# EARS.net
KiCad netlist of a schematic drawn in EAGLE
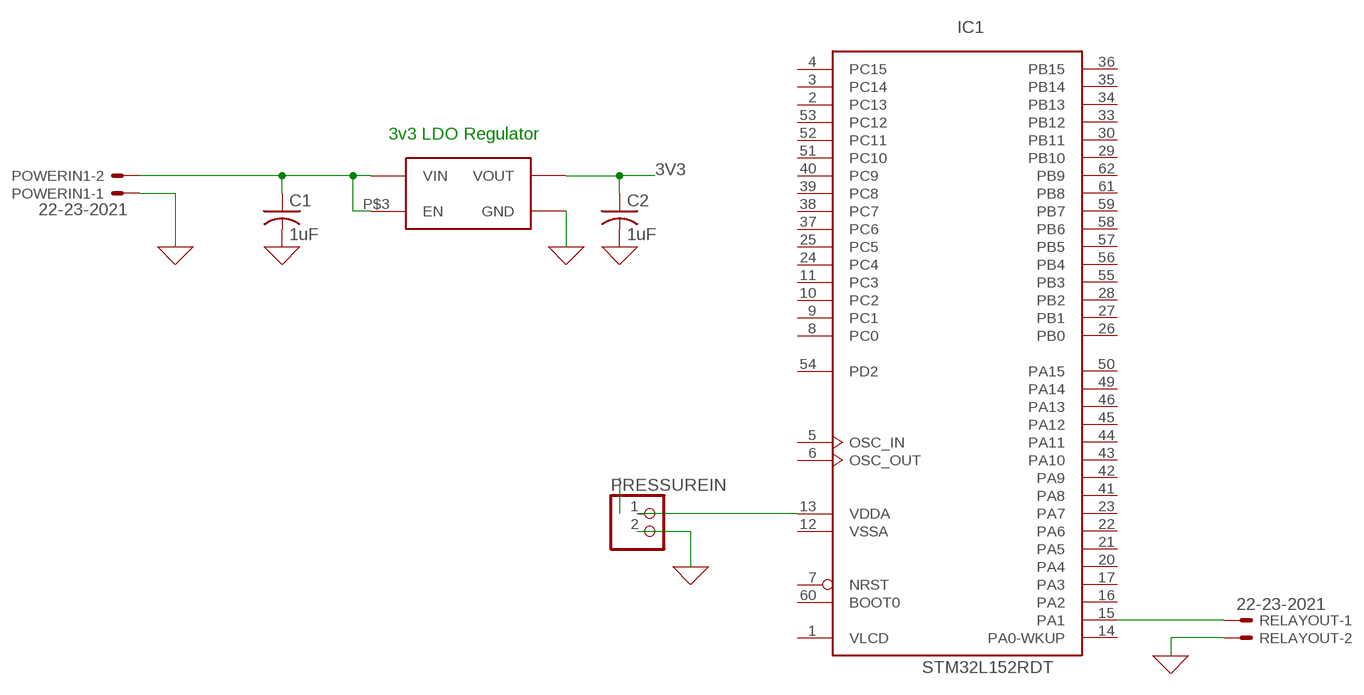
[diagram p0: schematic, sheet 1]

(export (version "E")
  (design (tool "Eeschema 10.0.6"))
  (components
    (comp (ref "3V3REG")
      (value "NCP551")
      (footprint "eagle-import:5-TSOP")
      (libsource (lib "eagle-import") (part "NCP551"))
    )
    (comp (ref "C1")
      (value "1uF")
      (footprint "eagle-import:C0603")
      (libsource (lib "eagle-import") (part "C-USC0603"))
    )
    (comp (ref "C2")
      (value "1uF")
      (footprint "eagle-import:C0603")
      (libsource (lib "eagle-import") (part "C-USC0603"))
    )
    (comp (ref "IC1")
      (value "STM32L152RDT")
      (footprint "eagle-import:LQFP64")
      (libsource (lib "eagle-import") (part "STM32L152RTD"))
    )
    (comp (ref "POWERIN1")
      (value "22-23-2021")
      (footprint "eagle-import:22-23-2021")
      (fields (field (name "MF") "MOLEX"))
      (libsource (lib "eagle-import") (part "22-23-2021"))
    )
    (comp (ref "PRESSUREIN")
      (value "PINHD-1X2")
      (footprint "eagle-import:1X02")
      (libsource (lib "eagle-import") (part "PINHD-1X2"))
    )
    (comp (ref "RELAYOUT")
      (value "22-23-2021")
      (footprint "eagle-import:22-23-2021")
      (fields (field (name "MF") "MOLEX"))
      (libsource (lib "eagle-import") (part "22-23-2021"))
    )
  )
  (nets
    (net (code "1") (name "/3V3") (class "Default")
      (node (ref "3V3REG") (pin "P$5") (pinfunction "VOUT_P$5") (pintype "bidirectional"))
      (node (ref "C2") (pin "1") (pinfunction "1_1") (pintype "passive"))
    )
    (net (code "2") (name "/VLCD") (class "Default")
      (node (ref "IC1") (pin "1") (pinfunction "VLCD_1") (pintype "power_in"))
    )
    (net (code "3") (name "/VSSA") (class "Default")
      (node (ref "IC1") (pin "12") (pinfunction "VSSA_12") (pintype "power_in"))
    )
    (net (code "4") (name "GND") (class "Default")
      (node (ref "3V3REG") (pin "P$1") (pinfunction "GND_P$1") (pintype "bidirectional"))
      (node (ref "C1") (pin "2") (pinfunction "2_2") (pintype "passive"))
      (node (ref "C2") (pin "2") (pinfunction "2_2") (pintype "passive"))
      (node (ref "POWERIN1") (pin "1") (pinfunction "S_1") (pintype "passive"))
      (node (ref "PRESSUREIN") (pin "2") (pinfunction "2_2") (pintype "passive"))
      (node (ref "RELAYOUT") (pin "2") (pinfunction "S_2") (pintype "passive"))
    )
    (net (code "5") (name "Net-(3V3REG-EN)") (class "Default")
      (node (ref "3V3REG") (pin "P$2") (pinfunction "VIN_P$2") (pintype "bidirectional"))
      (node (ref "3V3REG") (pin "P$3") (pinfunction "EN_P$3") (pintype "bidirectional"))
      (node (ref "C1") (pin "1") (pinfunction "1_1") (pintype "passive"))
      (node (ref "POWERIN1") (pin "2") (pinfunction "S_2") (pintype "passive"))
    )
    (net (code "6") (name "Net-(IC1A-PA1)") (class "Default")
      (node (ref "IC1") (pin "15") (pinfunction "PA1_15") (pintype "bidirectional"))
      (node (ref "RELAYOUT") (pin "1") (pinfunction "S_1") (pintype "passive"))
    )
    (net (code "7") (name "Net-(IC1A-VDDA)") (class "Default")
      (node (ref "IC1") (pin "13") (pinfunction "VDDA_13") (pintype "power_in"))
      (node (ref "PRESSUREIN") (pin "1") (pinfunction "1_1") (pintype "passive"))
    )
    (net (code "8") (name "unconnected-(IC1A-BOOT0-Pad60)") (class "Default")
      (node (ref "IC1") (pin "60") (pinfunction "BOOT0_60") (pintype "input"))
    )
    (net (code "9") (name "unconnected-(IC1A-NRST-Pad7)") (class "Default")
      (node (ref "IC1") (pin "7") (pinfunction "NRST_7") (pintype "bidirectional"))
    )
    (net (code "10") (name "unconnected-(IC1A-OSC_IN-Pad5)") (class "Default")
      (node (ref "IC1") (pin "5") (pinfunction "OSC_IN_5") (pintype "bidirectional"))
    )
    (net (code "11") (name "unconnected-(IC1A-OSC_OUT-Pad6)") (class "Default")
      (node (ref "IC1") (pin "6") (pinfunction "OSC_OUT_6") (pintype "bidirectional"))
    )
    (net (code "12") (name "unconnected-(IC1A-PA0-WKUP-Pad14)") (class "Default")
      (node (ref "IC1") (pin "14") (pinfunction "PA0-WKUP_14") (pintype "bidirectional"))
    )
    (net (code "13") (name "unconnected-(IC1A-PA2-Pad16)") (class "Default")
      (node (ref "IC1") (pin "16") (pinfunction "PA2_16") (pintype "bidirectional"))
    )
    (net (code "14") (name "unconnected-(IC1A-PA3-Pad17)") (class "Default")
      (node (ref "IC1") (pin "17") (pinfunction "PA3_17") (pintype "bidirectional"))
    )
    (net (code "15") (name "unconnected-(IC1A-PA4-Pad20)") (class "Default")
      (node (ref "IC1") (pin "20") (pinfunction "PA4_20") (pintype "bidirectional"))
    )
    (net (code "16") (name "unconnected-(IC1A-PA5-Pad21)") (class "Default")
      (node (ref "IC1") (pin "21") (pinfunction "PA5_21") (pintype "bidirectional"))
    )
    (net (code "17") (name "unconnected-(IC1A-PA6-Pad22)") (class "Default")
      (node (ref "IC1") (pin "22") (pinfunction "PA6_22") (pintype "bidirectional"))
    )
    (net (code "18") (name "unconnected-(IC1A-PA7-Pad23)") (class "Default")
      (node (ref "IC1") (pin "23") (pinfunction "PA7_23") (pintype "bidirectional"))
    )
    (net (code "19") (name "unconnected-(IC1A-PA8-Pad41)") (class "Default")
      (node (ref "IC1") (pin "41") (pinfunction "PA8_41") (pintype "bidirectional"))
    )
    (net (code "20") (name "unconnected-(IC1A-PA9-Pad42)") (class "Default")
      (node (ref "IC1") (pin "42") (pinfunction "PA9_42") (pintype "bidirectional"))
    )
    (net (code "21") (name "unconnected-(IC1A-PA10-Pad43)") (class "Default")
      (node (ref "IC1") (pin "43") (pinfunction "PA10_43") (pintype "bidirectional"))
    )
    (net (code "22") (name "unconnected-(IC1A-PA11-Pad44)") (class "Default")
      (node (ref "IC1") (pin "44") (pinfunction "PA11_44") (pintype "bidirectional"))
    )
    (net (code "23") (name "unconnected-(IC1A-PA12-Pad45)") (class "Default")
      (node (ref "IC1") (pin "45") (pinfunction "PA12_45") (pintype "bidirectional"))
    )
    (net (code "24") (name "unconnected-(IC1A-PA13-Pad46)") (class "Default")
      (node (ref "IC1") (pin "46") (pinfunction "PA13_46") (pintype "bidirectional"))
    )
    (net (code "25") (name "unconnected-(IC1A-PA14-Pad49)") (class "Default")
      (node (ref "IC1") (pin "49") (pinfunction "PA14_49") (pintype "bidirectional"))
    )
    (net (code "26") (name "unconnected-(IC1A-PA15-Pad50)") (class "Default")
      (node (ref "IC1") (pin "50") (pinfunction "PA15_50") (pintype "bidirectional"))
    )
    (net (code "27") (name "unconnected-(IC1A-PB0-Pad26)") (class "Default")
      (node (ref "IC1") (pin "26") (pinfunction "PB0_26") (pintype "bidirectional"))
    )
    (net (code "28") (name "unconnected-(IC1A-PB1-Pad27)") (class "Default")
      (node (ref "IC1") (pin "27") (pinfunction "PB1_27") (pintype "bidirectional"))
    )
    (net (code "29") (name "unconnected-(IC1A-PB2-Pad28)") (class "Default")
      (node (ref "IC1") (pin "28") (pinfunction "PB2_28") (pintype "bidirectional"))
    )
    (net (code "30") (name "unconnected-(IC1A-PB3-Pad55)") (class "Default")
      (node (ref "IC1") (pin "55") (pinfunction "PB3_55") (pintype "bidirectional"))
    )
    (net (code "31") (name "unconnected-(IC1A-PB4-Pad56)") (class "Default")
      (node (ref "IC1") (pin "56") (pinfunction "PB4_56") (pintype "bidirectional"))
    )
    (net (code "32") (name "unconnected-(IC1A-PB5-Pad57)") (class "Default")
      (node (ref "IC1") (pin "57") (pinfunction "PB5_57") (pintype "bidirectional"))
    )
    (net (code "33") (name "unconnected-(IC1A-PB6-Pad58)") (class "Default")
      (node (ref "IC1") (pin "58") (pinfunction "PB6_58") (pintype "bidirectional"))
    )
    (net (code "34") (name "unconnected-(IC1A-PB7-Pad59)") (class "Default")
      (node (ref "IC1") (pin "59") (pinfunction "PB7_59") (pintype "bidirectional"))
    )
    (net (code "35") (name "unconnected-(IC1A-PB8-Pad61)") (class "Default")
      (node (ref "IC1") (pin "61") (pinfunction "PB8_61") (pintype "bidirectional"))
    )
    (net (code "36") (name "unconnected-(IC1A-PB9-Pad62)") (class "Default")
      (node (ref "IC1") (pin "62") (pinfunction "PB9_62") (pintype "bidirectional"))
    )
    (net (code "37") (name "unconnected-(IC1A-PB10-Pad29)") (class "Default")
      (node (ref "IC1") (pin "29") (pinfunction "PB10_29") (pintype "bidirectional"))
    )
    (net (code "38") (name "unconnected-(IC1A-PB11-Pad30)") (class "Default")
      (node (ref "IC1") (pin "30") (pinfunction "PB11_30") (pintype "bidirectional"))
    )
    (net (code "39") (name "unconnected-(IC1A-PB12-Pad33)") (class "Default")
      (node (ref "IC1") (pin "33") (pinfunction "PB12_33") (pintype "bidirectional"))
    )
    (net (code "40") (name "unconnected-(IC1A-PB13-Pad34)") (class "Default")
      (node (ref "IC1") (pin "34") (pinfunction "PB13_34") (pintype "bidirectional"))
    )
    (net (code "41") (name "unconnected-(IC1A-PB14-Pad35)") (class "Default")
      (node (ref "IC1") (pin "35") (pinfunction "PB14_35") (pintype "bidirectional"))
    )
    (net (code "42") (name "unconnected-(IC1A-PB15-Pad36)") (class "Default")
      (node (ref "IC1") (pin "36") (pinfunction "PB15_36") (pintype "bidirectional"))
    )
    (net (code "43") (name "unconnected-(IC1A-PC0-Pad8)") (class "Default")
      (node (ref "IC1") (pin "8") (pinfunction "PC0_8") (pintype "bidirectional"))
    )
    (net (code "44") (name "unconnected-(IC1A-PC1-Pad9)") (class "Default")
      (node (ref "IC1") (pin "9") (pinfunction "PC1_9") (pintype "bidirectional"))
    )
    (net (code "45") (name "unconnected-(IC1A-PC2-Pad10)") (class "Default")
      (node (ref "IC1") (pin "10") (pinfunction "PC2_10") (pintype "bidirectional"))
    )
    (net (code "46") (name "unconnected-(IC1A-PC3-Pad11)") (class "Default")
      (node (ref "IC1") (pin "11") (pinfunction "PC3_11") (pintype "bidirectional"))
    )
    (net (code "47") (name "unconnected-(IC1A-PC4-Pad24)") (class "Default")
      (node (ref "IC1") (pin "24") (pinfunction "PC4_24") (pintype "bidirectional"))
    )
    (net (code "48") (name "unconnected-(IC1A-PC5-Pad25)") (class "Default")
      (node (ref "IC1") (pin "25") (pinfunction "PC5_25") (pintype "bidirectional"))
    )
    (net (code "49") (name "unconnected-(IC1A-PC6-Pad37)") (class "Default")
      (node (ref "IC1") (pin "37") (pinfunction "PC6_37") (pintype "bidirectional"))
    )
    (net (code "50") (name "unconnected-(IC1A-PC7-Pad38)") (class "Default")
      (node (ref "IC1") (pin "38") (pinfunction "PC7_38") (pintype "bidirectional"))
    )
    (net (code "51") (name "unconnected-(IC1A-PC8-Pad39)") (class "Default")
      (node (ref "IC1") (pin "39") (pinfunction "PC8_39") (pintype "bidirectional"))
    )
    (net (code "52") (name "unconnected-(IC1A-PC9-Pad40)") (class "Default")
      (node (ref "IC1") (pin "40") (pinfunction "PC9_40") (pintype "bidirectional"))
    )
    (net (code "53") (name "unconnected-(IC1A-PC10-Pad51)") (class "Default")
      (node (ref "IC1") (pin "51") (pinfunction "PC10_51") (pintype "bidirectional"))
    )
    (net (code "54") (name "unconnected-(IC1A-PC11-Pad52)") (class "Default")
      (node (ref "IC1") (pin "52") (pinfunction "PC11_52") (pintype "bidirectional"))
    )
    (net (code "55") (name "unconnected-(IC1A-PC12-Pad53)") (class "Default")
      (node (ref "IC1") (pin "53") (pinfunction "PC12_53") (pintype "bidirectional"))
    )
    (net (code "56") (name "unconnected-(IC1A-PC13-Pad2)") (class "Default")
      (node (ref "IC1") (pin "2") (pinfunction "PC13_2") (pintype "bidirectional"))
    )
    (net (code "57") (name "unconnected-(IC1A-PC14-Pad3)") (class "Default")
      (node (ref "IC1") (pin "3") (pinfunction "PC14_3") (pintype "bidirectional"))
    )
    (net (code "58") (name "unconnected-(IC1A-PC15-Pad4)") (class "Default")
      (node (ref "IC1") (pin "4") (pinfunction "PC15_4") (pintype "bidirectional"))
    )
    (net (code "59") (name "unconnected-(IC1A-PD2-Pad54)") (class "Default")
      (node (ref "IC1") (pin "54") (pinfunction "PD2_54") (pintype "bidirectional"))
    )
  )
)
